# 06_GPIO.net
KiCad netlist of a schematic drawn in Altium Designer
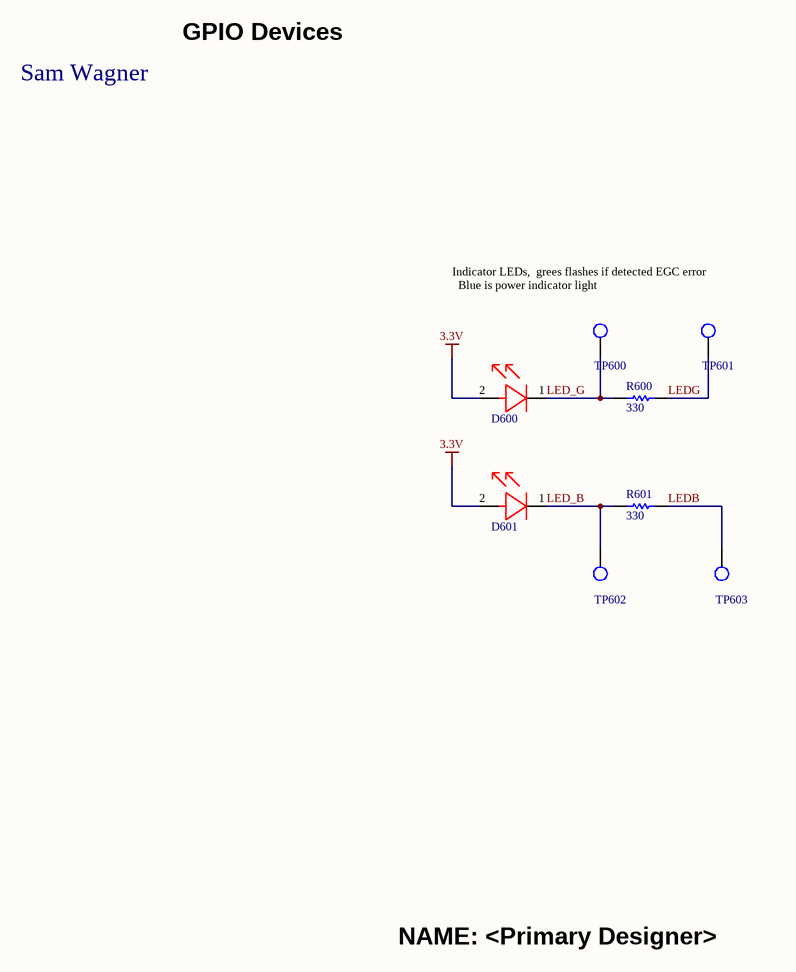
[diagram p0: 06_GPIO.SchDoc]

(export (version "E")
  (design (tool "Eeschema 10.0.6"))
  (components
    (comp (ref "D600")
      (value "LED_RED_0805.1")
      (footprint "LED_RED_0805")
      (description "LED SUPER RED CLR THIN 0805 SMD")
      (fields
        (field (name "MANUFACTURER") "Vishay / Lite-On")
        (field (name "MANUFACTURER PART NUMBER") "LTST-C171KRKT")
      )
      (libsource (lib "ece315-S20") (part "LED_RED_0805.1"))
    )
    (comp (ref "D601")
      (value "LED_RED_0805.1")
      (footprint "LED_RED_0805")
      (description "LED SUPER RED CLR THIN 0805 SMD")
      (fields
        (field (name "MANUFACTURER") "Vishay / Lite-On")
        (field (name "MANUFACTURER PART NUMBER") "LTST-C171KRKT")
      )
      (libsource (lib "ece315-S20") (part "LED_RED_0805.1"))
    )
    (comp (ref "R600")
      (value "330")
      (footprint "RES_0805")
      (description "RES SMD 330 OHM 1% 1/8W 0805")
      (fields
        (field (name "MANUFACTURER") "Panasonic / Panasonic ECG")
        (field (name "MANUFACTURER PART NUMBER") "ERJ-6ENF3300V")
        (field (name "RESISTANCE") "330")
      )
      (libsource (lib "ece315-S20") (part "RES_0805_R_330.00"))
    )
    (comp (ref "R601")
      (value "330")
      (footprint "RES_0805")
      (description "RES SMD 330 OHM 1% 1/8W 0805")
      (fields
        (field (name "MANUFACTURER") "Panasonic / Panasonic ECG")
        (field (name "MANUFACTURER PART NUMBER") "ERJ-6ENF3300V")
        (field (name "RESISTANCE") "330")
      )
      (libsource (lib "ece315-S20") (part "RES_0805_R_330.00"))
    )
    (comp (ref "TP600")
      (value "TP_1206")
      (footprint "TP-SMC-1206")
      (description "Test Point SMD 1206")
      (fields
        (field (name "MANUFACTURER") "TE Connectivity (Tyco Electronics)")
        (field (name "MANUFACTURER PART NUMBER") "1625854-1")
      )
      (libsource (lib "ece315-S20") (part "TP_1206"))
    )
    (comp (ref "TP601")
      (value "TP_1206")
      (footprint "TP-SMC-1206")
      (description "Test Point SMD 1206")
      (fields
        (field (name "MANUFACTURER") "TE Connectivity (Tyco Electronics)")
        (field (name "MANUFACTURER PART NUMBER") "1625854-1")
      )
      (libsource (lib "ece315-S20") (part "TP_1206"))
    )
    (comp (ref "TP602")
      (value "TP_1206")
      (footprint "TP-SMC-1206")
      (description "Test Point SMD 1206")
      (fields
        (field (name "MANUFACTURER") "TE Connectivity (Tyco Electronics)")
        (field (name "MANUFACTURER PART NUMBER") "1625854-1")
      )
      (libsource (lib "ece315-S20") (part "TP_1206"))
    )
    (comp (ref "TP603")
      (value "TP_1206")
      (footprint "TP-SMC-1206")
      (description "Test Point SMD 1206")
      (fields
        (field (name "MANUFACTURER") "TE Connectivity (Tyco Electronics)")
        (field (name "MANUFACTURER PART NUMBER") "1625854-1")
      )
      (libsource (lib "ece315-S20") (part "TP_1206"))
    )
  )
  (nets
    (net (code "1") (name "/LEDB") (class "Default")
      (node (ref "R601") (pin "2") (pinfunction "2_2") (pintype "passive"))
      (node (ref "TP603") (pin "1") (pintype "passive"))
    )
    (net (code "2") (name "/LEDG") (class "Default")
      (node (ref "R600") (pin "2") (pinfunction "2_2") (pintype "passive"))
      (node (ref "TP601") (pin "1") (pintype "passive"))
    )
    (net (code "3") (name "/LED_B") (class "Default")
      (node (ref "D601") (pin "1") (pinfunction "Cathode_1") (pintype "passive"))
      (node (ref "R601") (pin "1") (pinfunction "1_1") (pintype "passive"))
      (node (ref "TP602") (pin "1") (pintype "passive"))
    )
    (net (code "4") (name "/LED_G") (class "Default")
      (node (ref "D600") (pin "1") (pinfunction "Cathode_1") (pintype "passive"))
      (node (ref "R600") (pin "1") (pinfunction "1_1") (pintype "passive"))
      (node (ref "TP600") (pin "1") (pintype "passive"))
    )
    (net (code "5") (name "3.3V") (class "Default")
      (node (ref "D600") (pin "2") (pinfunction "Anode_2") (pintype "passive"))
      (node (ref "D601") (pin "2") (pinfunction "Anode_2") (pintype "passive"))
    )
  )
)
